# DRL.net
KiCad netlist of a schematic drawn in Altium Designer
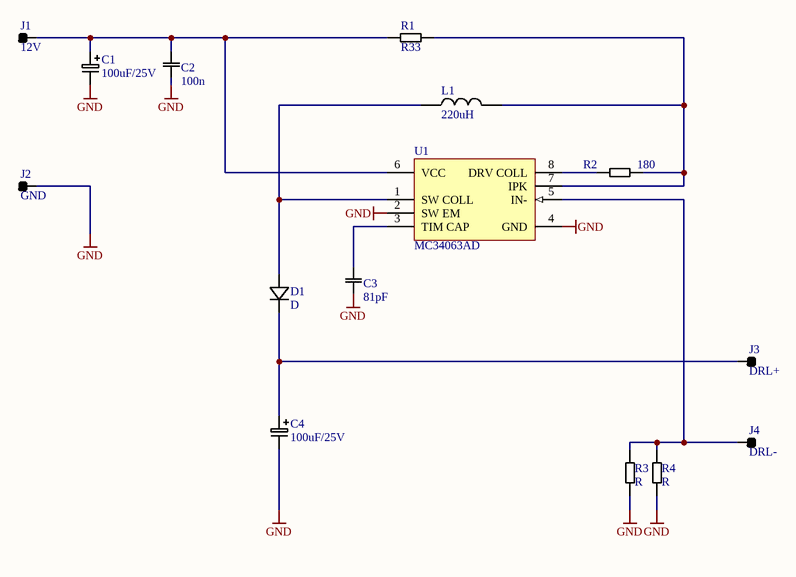
[diagram p0: DRL.SchDoc]

(export (version "E")
  (design (tool "Eeschema 10.0.6"))
  (components
    (comp (ref "C1")
      (value "100uF/25V")
      (footprint "CAPC7238N")
      (libsource (lib "ABU_standard") (part "C_EL"))
    )
    (comp (ref "C2")
      (value "100n")
      (footprint "ABU_standard:C0805")
      (libsource (lib "ABU_standard") (part "C"))
    )
    (comp (ref "C3")
      (value "81pF")
      (footprint "ABU_standard:C0805")
      (libsource (lib "ABU_standard") (part "C"))
    )
    (comp (ref "C4")
      (value "100uF/25V")
      (footprint "CAPC7238N")
      (libsource (lib "ABU_standard") (part "C_EL"))
    )
    (comp (ref "D1") (value "D") (footprint "ABU_standard:SMA") (libsource (lib "ABU_standard") (part "D")))
    (comp (ref "J1") (value "12V") (footprint "PIN") (libsource (lib "") (part "PIN_1")))
    (comp (ref "J2") (value "GND") (footprint "PIN") (libsource (lib "") (part "PIN_1")))
    (comp (ref "J3") (value "DRL+") (footprint "PIN") (libsource (lib "ABU_standard") (part "PIN")))
    (comp (ref "J4") (value "DRL-") (footprint "PIN") (libsource (lib "ABU_standard") (part "PIN")))
    (comp (ref "L1") (value "220uH") (footprint "IND Coilcraft") (libsource (lib "Private") (part "L")))
    (comp (ref "R1") (value "R33") (footprint "R1206") (libsource (lib "ABU_standard") (part "R")))
    (comp (ref "R2") (value "180") (footprint "R0805") (libsource (lib "ABU_standard") (part "R")))
    (comp (ref "R3") (value "R") (footprint "R1206") (libsource (lib "") (part "R_1")))
    (comp (ref "R4") (value "R") (footprint "R1206") (libsource (lib "") (part "R_1")))
    (comp (ref "U1")
      (value "MC34063AD")
      (footprint "ABU_standard:SO8")
      (description "DC-to-DC Converter Control Circuit")
      (fields (field (name "PUBLISHER") "Altium Limited"))
      (libsource (lib "ON Semi Power Mgt DC-DC Converter") (part "MC34063AD"))
    )
  )
  (nets
    (net (code "1") (name "GND") (class "Default")
      (node (ref "C1") (pin "2") (pinfunction "2_2") (pintype "passive"))
      (node (ref "C2") (pin "1") (pinfunction "1_1") (pintype "passive"))
      (node (ref "C3") (pin "1") (pinfunction "1_1") (pintype "passive"))
      (node (ref "C4") (pin "2") (pinfunction "2_2") (pintype "passive"))
      (node (ref "J2") (pin "1") (pinfunction "1_1") (pintype "passive"))
      (node (ref "R3") (pin "2") (pinfunction "2_2") (pintype "passive"))
      (node (ref "R4") (pin "2") (pinfunction "2_2") (pintype "passive"))
      (node (ref "U1") (pin "2") (pinfunction "SW_EM_2") (pintype "passive"))
      (node (ref "U1") (pin "4") (pinfunction "GND_4") (pintype "power_in"))
    )
    (net (code "2") (name "Net-(C4-Pad1)") (class "Default")
      (node (ref "C4") (pin "1") (pinfunction "1_1") (pintype "passive"))
      (node (ref "D1") (pin "C") (pinfunction "C_C") (pintype "passive"))
      (node (ref "J3") (pin "1") (pinfunction "1_1") (pintype "passive"))
    )
    (net (code "3") (name "Net-(U1-DRV_COLL)") (class "Default")
      (node (ref "R2") (pin "2") (pinfunction "2_2") (pintype "passive"))
      (node (ref "U1") (pin "8") (pinfunction "DRV_COLL_8") (pintype "open_collector"))
    )
    (net (code "4") (name "Net-(U1-IN-)") (class "Default")
      (node (ref "J4") (pin "1") (pinfunction "1_1") (pintype "passive"))
      (node (ref "R3") (pin "1") (pinfunction "1_1") (pintype "passive"))
      (node (ref "R4") (pin "1") (pinfunction "1_1") (pintype "passive"))
      (node (ref "U1") (pin "5") (pinfunction "IN-_5") (pintype "input"))
    )
    (net (code "5") (name "Net-(U1-IPK)") (class "Default")
      (node (ref "L1") (pin "2") (pinfunction "2_2") (pintype "passive"))
      (node (ref "R1") (pin "1") (pinfunction "1_1") (pintype "passive"))
      (node (ref "R2") (pin "1") (pinfunction "1_1") (pintype "passive"))
      (node (ref "U1") (pin "7") (pinfunction "IPK_7") (pintype "passive"))
    )
    (net (code "6") (name "Net-(U1-SW_COLL)") (class "Default")
      (node (ref "D1") (pin "A") (pinfunction "A_A") (pintype "passive"))
      (node (ref "L1") (pin "1") (pinfunction "1_1") (pintype "passive"))
      (node (ref "U1") (pin "1") (pinfunction "SW_COLL_1") (pintype "passive"))
    )
    (net (code "7") (name "Net-(U1-TIM_CAP)") (class "Default")
      (node (ref "C3") (pin "2") (pinfunction "2_2") (pintype "passive"))
      (node (ref "U1") (pin "3") (pinfunction "TIM_CAP_3") (pintype "passive"))
    )
    (net (code "8") (name "Net-(U1-VCC)") (class "Default")
      (node (ref "C1") (pin "1") (pinfunction "1_1") (pintype "passive"))
      (node (ref "C2") (pin "2") (pinfunction "2_2") (pintype "passive"))
      (node (ref "J1") (pin "1") (pinfunction "1_1") (pintype "passive"))
      (node (ref "R1") (pin "2") (pinfunction "2_2") (pintype "passive"))
      (node (ref "U1") (pin "6") (pinfunction "VCC_6") (pintype "power_in"))
    )
  )
)
